# SoilMoisture.net
KiCad netlist of a schematic drawn in EAGLE
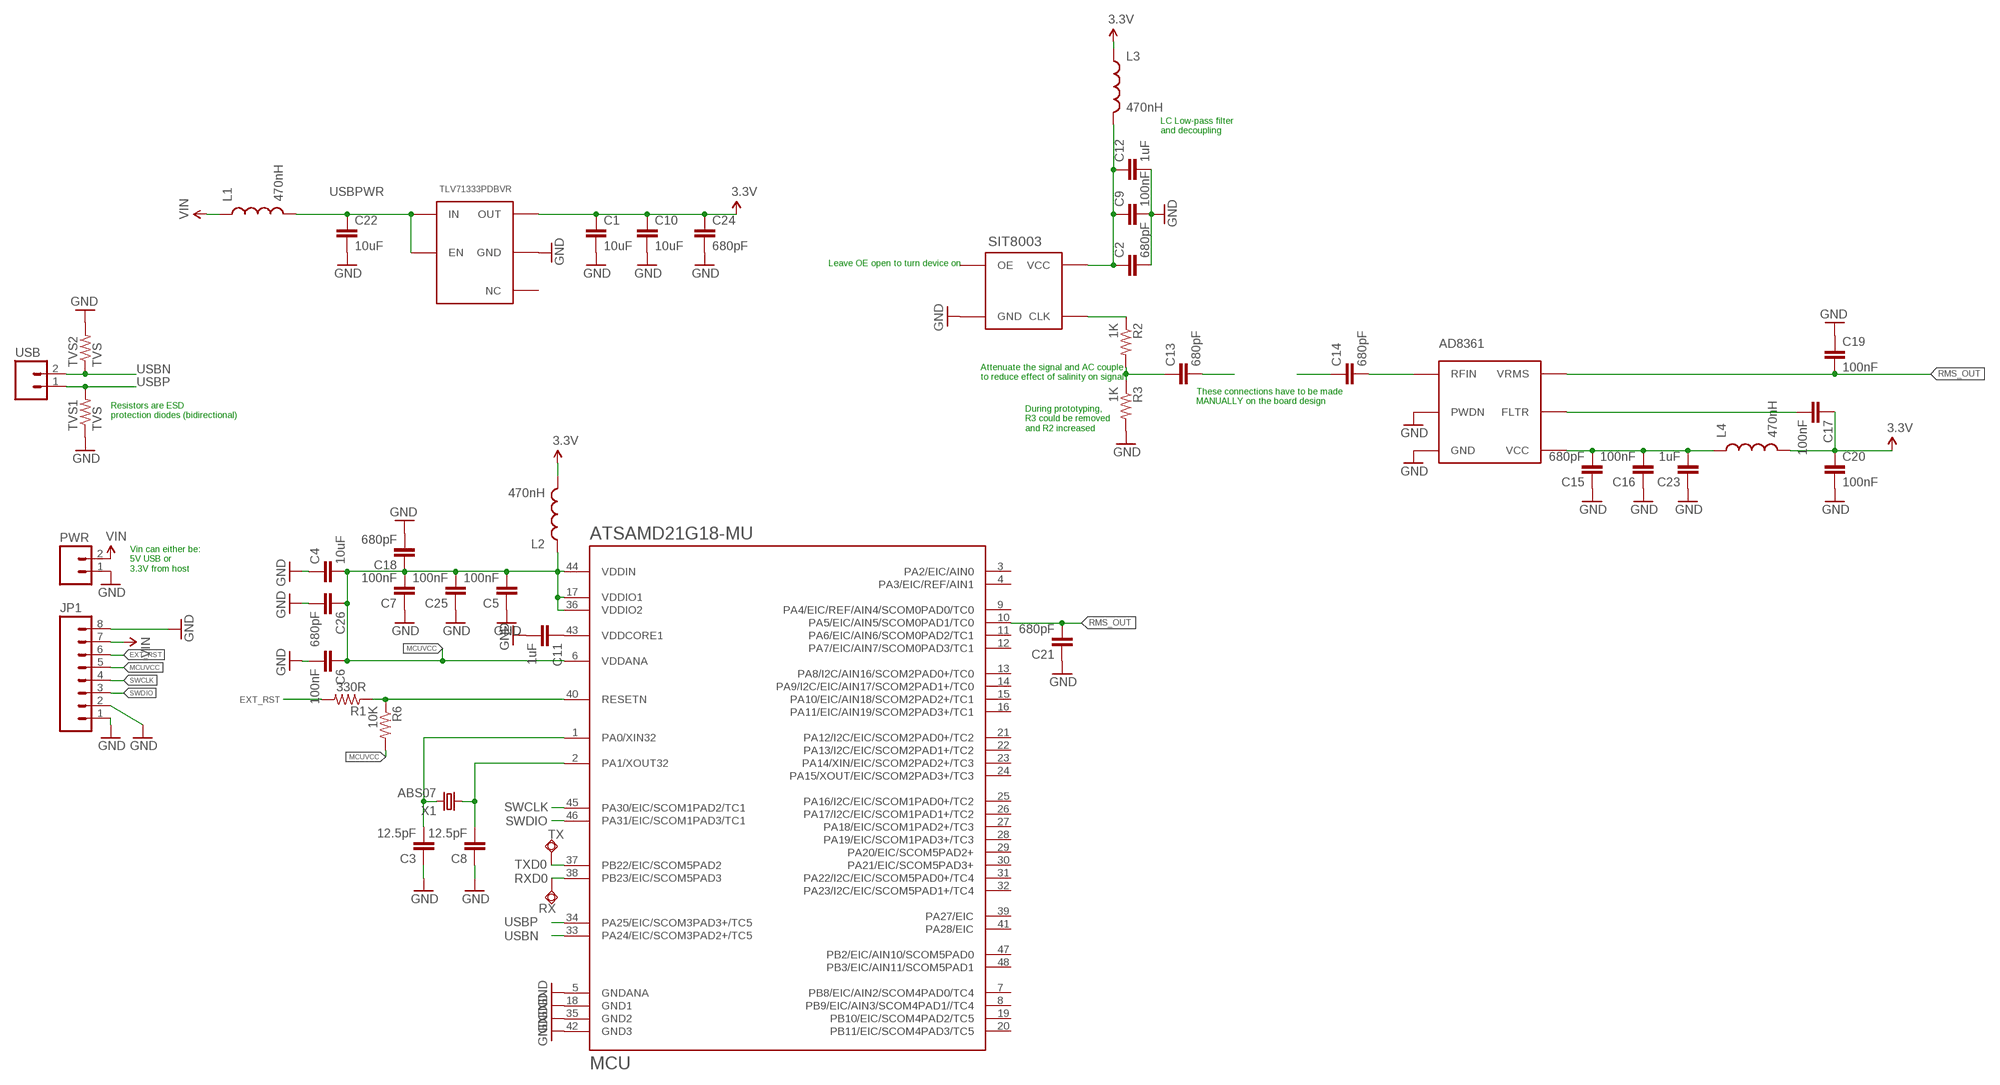
[diagram p0: schematic, sheet 1]

(export (version "E")
  (design (tool "Eeschema 10.0.6"))
  (components
    (comp (ref "AD8361")
      (value "AD8361")
      (footprint "eagle-import:SOT23-6")
      (libsource (lib "eagle-import") (part "AD8361"))
    )
    (comp (ref "C1")
      (value "10uF")
      (footprint "eagle-import:C0603")
      (libsource (lib "eagle-import") (part "C_0603"))
    )
    (comp (ref "C2")
      (value "680pF")
      (footprint "eagle-import:0402-CAP")
      (libsource (lib "eagle-import") (part "CAP0402-CAP"))
    )
    (comp (ref "C3")
      (value "12.5pF")
      (footprint "eagle-import:0402-CAP")
      (libsource (lib "eagle-import") (part "CAP0402-CAP"))
    )
    (comp (ref "C4")
      (value "10uF")
      (footprint "eagle-import:C0603")
      (libsource (lib "eagle-import") (part "C_0603"))
    )
    (comp (ref "C5")
      (value "100nF")
      (footprint "eagle-import:0402-CAP")
      (libsource (lib "eagle-import") (part "CAP0402-CAP"))
    )
    (comp (ref "C6")
      (value "100nF")
      (footprint "eagle-import:0402-CAP")
      (libsource (lib "eagle-import") (part "CAP0402-CAP"))
    )
    (comp (ref "C7")
      (value "100nF")
      (footprint "eagle-import:0402-CAP")
      (libsource (lib "eagle-import") (part "CAP0402-CAP"))
    )
    (comp (ref "C8")
      (value "12.5pF")
      (footprint "eagle-import:0402-CAP")
      (libsource (lib "eagle-import") (part "CAP0402-CAP"))
    )
    (comp (ref "C9")
      (value "100nF")
      (footprint "eagle-import:0402-CAP")
      (libsource (lib "eagle-import") (part "CAP0402-CAP"))
    )
    (comp (ref "C10")
      (value "10uF")
      (footprint "eagle-import:C0603")
      (libsource (lib "eagle-import") (part "C_0603"))
    )
    (comp (ref "C11")
      (value "1uF")
      (footprint "eagle-import:0402-CAP")
      (libsource (lib "eagle-import") (part "CAP0402-CAP"))
    )
    (comp (ref "C12")
      (value "1uF")
      (footprint "eagle-import:0402-CAP")
      (libsource (lib "eagle-import") (part "CAP0402-CAP"))
    )
    (comp (ref "C13")
      (value "680pF")
      (footprint "eagle-import:0402-CAP")
      (libsource (lib "eagle-import") (part "CAP0402-CAP"))
    )
    (comp (ref "C14")
      (value "680pF")
      (footprint "eagle-import:0402-CAP")
      (libsource (lib "eagle-import") (part "CAP0402-CAP"))
    )
    (comp (ref "C15")
      (value "680pF")
      (footprint "eagle-import:0402-CAP")
      (libsource (lib "eagle-import") (part "CAP0402-CAP"))
    )
    (comp (ref "C16")
      (value "100nF")
      (footprint "eagle-import:0402-CAP")
      (libsource (lib "eagle-import") (part "CAP0402-CAP"))
    )
    (comp (ref "C17")
      (value "100nF")
      (footprint "eagle-import:0402-CAP")
      (libsource (lib "eagle-import") (part "CAP0402-CAP"))
    )
    (comp (ref "C18")
      (value "680pF")
      (footprint "eagle-import:0402-CAP")
      (libsource (lib "eagle-import") (part "CAP0402-CAP"))
    )
    (comp (ref "C19")
      (value "100nF")
      (footprint "eagle-import:0402-CAP")
      (libsource (lib "eagle-import") (part "CAP0402-CAP"))
    )
    (comp (ref "C20")
      (value "100nF")
      (footprint "eagle-import:0402-CAP")
      (libsource (lib "eagle-import") (part "CAP0402-CAP"))
    )
    (comp (ref "C21")
      (value "680pF")
      (footprint "eagle-import:0402-CAP")
      (libsource (lib "eagle-import") (part "CAP0402-CAP"))
    )
    (comp (ref "C22")
      (value "10uF")
      (footprint "eagle-import:C0603")
      (libsource (lib "eagle-import") (part "C_0603"))
    )
    (comp (ref "C23")
      (value "1uF")
      (footprint "eagle-import:0402-CAP")
      (libsource (lib "eagle-import") (part "CAP0402-CAP"))
    )
    (comp (ref "C24")
      (value "680pF")
      (footprint "eagle-import:0402-CAP")
      (libsource (lib "eagle-import") (part "CAP0402-CAP"))
    )
    (comp (ref "C25")
      (value "100nF")
      (footprint "eagle-import:0402-CAP")
      (libsource (lib "eagle-import") (part "CAP0402-CAP"))
    )
    (comp (ref "C26")
      (value "680pF")
      (footprint "eagle-import:0402-CAP")
      (libsource (lib "eagle-import") (part "CAP0402-CAP"))
    )
    (comp (ref "JP1")
      (value "M08")
      (footprint "eagle-import:1X08_ROUND")
      (libsource (lib "eagle-import") (part "M08"))
    )
    (comp (ref "L1")
      (value "470nH")
      (footprint "eagle-import:0603")
      (libsource (lib "eagle-import") (part "INDUCTOR0603"))
    )
    (comp (ref "L2")
      (value "470nH")
      (footprint "eagle-import:0603")
      (libsource (lib "eagle-import") (part "INDUCTOR0603"))
    )
    (comp (ref "L3")
      (value "470nH")
      (footprint "eagle-import:0603")
      (libsource (lib "eagle-import") (part "INDUCTOR0603"))
    )
    (comp (ref "L4")
      (value "470nH")
      (footprint "eagle-import:0603")
      (libsource (lib "eagle-import") (part "INDUCTOR0603"))
    )
    (comp (ref "MCU")
      (value "ATSAMD21G18-MU")
      (footprint "eagle-import:QFN48")
      (libsource (lib "eagle-import") (part "ATSAMD21G18-MU"))
    )
    (comp (ref "PWR")
      (value "M02LOCK_LONGPADS")
      (footprint "eagle-import:1X02_LOCK_LONGPADS")
      (libsource (lib "eagle-import") (part "M02LOCK_LONGPADS"))
    )
    (comp (ref "R1")
      (value "330R")
      (footprint "eagle-import:0402-RES")
      (libsource (lib "eagle-import") (part "RESISTOR0402-RES"))
    )
    (comp (ref "R2")
      (value "1K")
      (footprint "eagle-import:0402-RES")
      (libsource (lib "eagle-import") (part "RESISTOR0402-RES"))
    )
    (comp (ref "R3")
      (value "1K")
      (footprint "eagle-import:0402-RES")
      (libsource (lib "eagle-import") (part "RESISTOR0402-RES"))
    )
    (comp (ref "R6")
      (value "10K")
      (footprint "eagle-import:0402-RES")
      (libsource (lib "eagle-import") (part "RESISTOR0402-RES"))
    )
    (comp (ref "REGULATOR")
      (value "TLV71333PDBVR")
      (footprint "eagle-import:TLV71333PDBVR")
      (libsource (lib "eagle-import") (part "TLV71333PDBVR"))
    )
    (comp (ref "RX")
      (value "TPSQTP20SQ")
      (footprint "eagle-import:TP20SQ")
      (libsource (lib "eagle-import") (part "TPSQTP20SQ"))
    )
    (comp (ref "SIT8003")
      (value "SIT8003")
      (footprint "eagle-import:SIT8003")
      (libsource (lib "eagle-import") (part "SIT8003"))
    )
    (comp (ref "TVS1")
      (value "TVS")
      (footprint "eagle-import:0402-RES")
      (libsource (lib "eagle-import") (part "RESISTOR0402-RES"))
    )
    (comp (ref "TVS2")
      (value "TVS")
      (footprint "eagle-import:0402-RES")
      (libsource (lib "eagle-import") (part "RESISTOR0402-RES"))
    )
    (comp (ref "TX")
      (value "TPSQTP20SQ")
      (footprint "eagle-import:TP20SQ")
      (libsource (lib "eagle-import") (part "TPSQTP20SQ"))
    )
    (comp (ref "USB")
      (value "M02LOCK_LONGPADS")
      (footprint "eagle-import:1X02_LOCK_LONGPADS")
      (libsource (lib "eagle-import") (part "M02LOCK_LONGPADS"))
    )
    (comp (ref "X1")
      (value "ABS07")
      (footprint "eagle-import:ABS07")
      (libsource (lib "eagle-import") (part "ABS07"))
    )
  )
  (nets
    (net (code "1") (name "/RXD0") (class "Default")
      (node (ref "MCU") (pin "38") (pinfunction "PB23/EIC/SCOM5PAD3_38") (pintype "bidirectional"))
      (node (ref "RX") (pin "TP") (pinfunction "TP_TP") (pintype "input"))
    )
    (net (code "2") (name "/TXD0") (class "Default")
      (node (ref "MCU") (pin "37") (pinfunction "PB22/EIC/SCOM5PAD2_37") (pintype "bidirectional"))
      (node (ref "TX") (pin "TP") (pinfunction "TP_TP") (pintype "input"))
    )
    (net (code "3") (name "/USBN") (class "Default")
      (node (ref "MCU") (pin "33") (pinfunction "PA24/EIC/SCOM3PAD2+/TC5_33") (pintype "bidirectional"))
      (node (ref "TVS2") (pin "1") (pinfunction "1_1") (pintype "passive"))
      (node (ref "USB") (pin "2") (pinfunction "2_2") (pintype "passive"))
    )
    (net (code "4") (name "/USBP") (class "Default")
      (node (ref "MCU") (pin "34") (pinfunction "PA25/EIC/SCOM3PAD3+/TC5_34") (pintype "bidirectional"))
      (node (ref "TVS1") (pin "2") (pinfunction "2_2") (pintype "passive"))
      (node (ref "USB") (pin "1") (pinfunction "1_1") (pintype "passive"))
    )
    (net (code "5") (name "/USBPWR") (class "Default")
      (node (ref "C22") (pin "1") (pinfunction "1_1") (pintype "passive"))
      (node (ref "L1") (pin "2") (pinfunction "2_2") (pintype "passive"))
      (node (ref "REGULATOR") (pin "P$1") (pinfunction "IN_P$1") (pintype "bidirectional"))
      (node (ref "REGULATOR") (pin "P$3") (pinfunction "EN_P$3") (pintype "bidirectional"))
    )
    (net (code "6") (name "3.3V") (class "Default")
      (node (ref "C1") (pin "1") (pinfunction "1_1") (pintype "passive"))
      (node (ref "C10") (pin "1") (pinfunction "1_1") (pintype "passive"))
      (node (ref "C17") (pin "1") (pinfunction "1_1") (pintype "passive"))
      (node (ref "C20") (pin "1") (pinfunction "1_1") (pintype "passive"))
      (node (ref "C24") (pin "1") (pinfunction "1_1") (pintype "passive"))
      (node (ref "L2") (pin "2") (pinfunction "2_2") (pintype "passive"))
      (node (ref "L3") (pin "1") (pinfunction "1_1") (pintype "passive"))
      (node (ref "L4") (pin "2") (pinfunction "2_2") (pintype "passive"))
      (node (ref "REGULATOR") (pin "P$5") (pinfunction "OUT_P$5") (pintype "bidirectional"))
    )
    (net (code "7") (name "EXT_RST") (class "Default")
      (node (ref "JP1") (pin "6") (pinfunction "6_6") (pintype "passive"))
      (node (ref "R1") (pin "2") (pinfunction "2_2") (pintype "passive"))
    )
    (net (code "8") (name "GND") (class "Default")
      (node (ref "AD8361") (pin "2") (pinfunction "GND_2") (pintype "bidirectional"))
      (node (ref "AD8361") (pin "4") (pinfunction "PWDN_4") (pintype "bidirectional"))
      (node (ref "C1") (pin "2") (pinfunction "2_2") (pintype "passive"))
      (node (ref "C10") (pin "2") (pinfunction "2_2") (pintype "passive"))
      (node (ref "C11") (pin "2") (pinfunction "2_2") (pintype "passive"))
      (node (ref "C12") (pin "2") (pinfunction "2_2") (pintype "passive"))
      (node (ref "C15") (pin "1") (pinfunction "1_1") (pintype "passive"))
      (node (ref "C16") (pin "1") (pinfunction "1_1") (pintype "passive"))
      (node (ref "C18") (pin "2") (pinfunction "2_2") (pintype "passive"))
      (node (ref "C19") (pin "1") (pinfunction "1_1") (pintype "passive"))
      (node (ref "C2") (pin "2") (pinfunction "2_2") (pintype "passive"))
      (node (ref "C20") (pin "2") (pinfunction "2_2") (pintype "passive"))
      (node (ref "C21") (pin "1") (pinfunction "1_1") (pintype "passive"))
      (node (ref "C22") (pin "2") (pinfunction "2_2") (pintype "passive"))
      (node (ref "C23") (pin "1") (pinfunction "1_1") (pintype "passive"))
      (node (ref "C24") (pin "2") (pinfunction "2_2") (pintype "passive"))
      (node (ref "C25") (pin "1") (pinfunction "1_1") (pintype "passive"))
      (node (ref "C26") (pin "2") (pinfunction "2_2") (pintype "passive"))
      (node (ref "C3") (pin "1") (pinfunction "1_1") (pintype "passive"))
      (node (ref "C4") (pin "1") (pinfunction "1_1") (pintype "passive"))
      (node (ref "C5") (pin "1") (pinfunction "1_1") (pintype "passive"))
      (node (ref "C6") (pin "2") (pinfunction "2_2") (pintype "passive"))
      (node (ref "C7") (pin "1") (pinfunction "1_1") (pintype "passive"))
      (node (ref "C8") (pin "1") (pinfunction "1_1") (pintype "passive"))
      (node (ref "C9") (pin "2") (pinfunction "2_2") (pintype "passive"))
      (node (ref "JP1") (pin "1") (pinfunction "1_1") (pintype "passive"))
      (node (ref "JP1") (pin "2") (pinfunction "2_2") (pintype "passive"))
      (node (ref "JP1") (pin "8") (pinfunction "8_8") (pintype "passive"))
      (node (ref "MCU") (pin "18") (pinfunction "GND1_18") (pintype "power_in"))
      (node (ref "MCU") (pin "35") (pinfunction "GND2_35") (pintype "power_in"))
      (node (ref "MCU") (pin "42") (pinfunction "GND3_42") (pintype "power_in"))
      (node (ref "MCU") (pin "5") (pinfunction "GNDANA_5") (pintype "power_in"))
      (node (ref "PWR") (pin "1") (pinfunction "1_1") (pintype "passive"))
      (node (ref "R3") (pin "2") (pinfunction "2_2") (pintype "passive"))
      (node (ref "REGULATOR") (pin "P$2") (pinfunction "GND_P$2") (pintype "bidirectional"))
      (node (ref "SIT8003") (pin "P$2") (pinfunction "GND_P$2") (pintype "bidirectional"))
      (node (ref "TVS1") (pin "1") (pinfunction "1_1") (pintype "passive"))
      (node (ref "TVS2") (pin "2") (pinfunction "2_2") (pintype "passive"))
    )
    (net (code "9") (name "MCUVCC") (class "Default")
      (node (ref "C18") (pin "1") (pinfunction "1_1") (pintype "passive"))
      (node (ref "C25") (pin "2") (pinfunction "2_2") (pintype "passive"))
      (node (ref "C26") (pin "1") (pinfunction "1_1") (pintype "passive"))
      (node (ref "C4") (pin "2") (pinfunction "2_2") (pintype "passive"))
      (node (ref "C5") (pin "2") (pinfunction "2_2") (pintype "passive"))
      (node (ref "C6") (pin "1") (pinfunction "1_1") (pintype "passive"))
      (node (ref "C7") (pin "2") (pinfunction "2_2") (pintype "passive"))
      (node (ref "JP1") (pin "5") (pinfunction "5_5") (pintype "passive"))
      (node (ref "L2") (pin "1") (pinfunction "1_1") (pintype "passive"))
      (node (ref "MCU") (pin "17") (pinfunction "VDDIO1_17") (pintype "power_in"))
      (node (ref "MCU") (pin "36") (pinfunction "VDDIO2_36") (pintype "power_in"))
      (node (ref "MCU") (pin "44") (pinfunction "VDDIN_44") (pintype "power_in"))
      (node (ref "MCU") (pin "6") (pinfunction "VDDANA_6") (pintype "power_in"))
      (node (ref "R6") (pin "2") (pinfunction "2_2") (pintype "passive"))
    )
    (net (code "10") (name "Net-(AD8361-FLTR)") (class "Default")
      (node (ref "AD8361") (pin "3") (pinfunction "FLTR_3") (pintype "bidirectional"))
      (node (ref "C17") (pin "2") (pinfunction "2_2") (pintype "passive"))
    )
    (net (code "11") (name "Net-(AD8361-RFIN)") (class "Default")
      (node (ref "AD8361") (pin "5") (pinfunction "RFIN_5") (pintype "bidirectional"))
      (node (ref "C14") (pin "2") (pinfunction "2_2") (pintype "passive"))
    )
    (net (code "12") (name "Net-(AD8361-VCC)") (class "Default")
      (node (ref "AD8361") (pin "6") (pinfunction "VCC_6") (pintype "bidirectional"))
      (node (ref "C15") (pin "2") (pinfunction "2_2") (pintype "passive"))
      (node (ref "C16") (pin "2") (pinfunction "2_2") (pintype "passive"))
      (node (ref "C23") (pin "2") (pinfunction "2_2") (pintype "passive"))
      (node (ref "L4") (pin "1") (pinfunction "1_1") (pintype "passive"))
    )
    (net (code "13") (name "Net-(C13-Pad1)") (class "Default")
      (node (ref "C13") (pin "1") (pinfunction "1_1") (pintype "passive"))
      (node (ref "R2") (pin "2") (pinfunction "2_2") (pintype "passive"))
      (node (ref "R3") (pin "1") (pinfunction "1_1") (pintype "passive"))
    )
    (net (code "14") (name "Net-(MCU-PA0{slash}XIN32)") (class "Default")
      (node (ref "C3") (pin "2") (pinfunction "2_2") (pintype "passive"))
      (node (ref "MCU") (pin "1") (pinfunction "PA0/XIN32_1") (pintype "bidirectional"))
      (node (ref "X1") (pin "P$2") (pinfunction "2_P$2") (pintype "passive"))
    )
    (net (code "15") (name "Net-(MCU-PA1{slash}XOUT32)") (class "Default")
      (node (ref "C8") (pin "2") (pinfunction "2_2") (pintype "passive"))
      (node (ref "MCU") (pin "2") (pinfunction "PA1/XOUT32_2") (pintype "bidirectional"))
      (node (ref "X1") (pin "P$1") (pinfunction "1_P$1") (pintype "passive"))
    )
    (net (code "16") (name "Net-(MCU-RESETN)") (class "Default")
      (node (ref "MCU") (pin "40") (pinfunction "RESETN_40") (pintype "bidirectional"))
      (node (ref "R1") (pin "1") (pinfunction "1_1") (pintype "passive"))
      (node (ref "R6") (pin "1") (pinfunction "1_1") (pintype "passive"))
    )
    (net (code "17") (name "Net-(MCU-VDDCORE1)") (class "Default")
      (node (ref "C11") (pin "1") (pinfunction "1_1") (pintype "passive"))
      (node (ref "MCU") (pin "43") (pinfunction "VDDCORE1_43") (pintype "input"))
    )
    (net (code "18") (name "Net-(SIT8003-CLK)") (class "Default")
      (node (ref "R2") (pin "1") (pinfunction "1_1") (pintype "passive"))
      (node (ref "SIT8003") (pin "P$3") (pinfunction "CLK_P$3") (pintype "bidirectional"))
    )
    (net (code "19") (name "Net-(SIT8003-VCC)") (class "Default")
      (node (ref "C12") (pin "1") (pinfunction "1_1") (pintype "passive"))
      (node (ref "C2") (pin "1") (pinfunction "1_1") (pintype "passive"))
      (node (ref "C9") (pin "1") (pinfunction "1_1") (pintype "passive"))
      (node (ref "L3") (pin "2") (pinfunction "2_2") (pintype "passive"))
      (node (ref "SIT8003") (pin "P$4") (pinfunction "VCC_P$4") (pintype "bidirectional"))
    )
    (net (code "20") (name "RMS_OUT") (class "Default")
      (node (ref "AD8361") (pin "1") (pinfunction "VRMS_1") (pintype "bidirectional"))
      (node (ref "C19") (pin "2") (pinfunction "2_2") (pintype "passive"))
      (node (ref "C21") (pin "2") (pinfunction "2_2") (pintype "passive"))
      (node (ref "MCU") (pin "10") (pinfunction "PA5/EIC/AIN5/SCOM0PAD1/TC0_10") (pintype "bidirectional"))
    )
    (net (code "21") (name "SWCLK") (class "Default")
      (node (ref "JP1") (pin "4") (pinfunction "4_4") (pintype "passive"))
      (node (ref "MCU") (pin "45") (pinfunction "PA30/EIC/SCOM1PAD2/TC1_45") (pintype "bidirectional"))
    )
    (net (code "22") (name "SWDIO") (class "Default")
      (node (ref "JP1") (pin "3") (pinfunction "3_3") (pintype "passive"))
      (node (ref "MCU") (pin "46") (pinfunction "PA31/EIC/SCOM1PAD3/TC1_46") (pintype "bidirectional"))
    )
    (net (code "23") (name "VIN") (class "Default")
      (node (ref "JP1") (pin "7") (pinfunction "7_7") (pintype "passive"))
      (node (ref "L1") (pin "1") (pinfunction "1_1") (pintype "passive"))
      (node (ref "PWR") (pin "2") (pinfunction "2_2") (pintype "passive"))
    )
    (net (code "24") (name "unconnected-(C13-Pad2)") (class "Default")
      (node (ref "C13") (pin "2") (pinfunction "2_2") (pintype "passive"))
    )
    (net (code "25") (name "unconnected-(C14-Pad1)") (class "Default")
      (node (ref "C14") (pin "1") (pinfunction "1_1") (pintype "passive"))
    )
    (net (code "26") (name "unconnected-(MCU-PA2{slash}EIC{slash}AIN0-Pad3)") (class "Default")
      (node (ref "MCU") (pin "3") (pinfunction "PA2/EIC/AIN0_3") (pintype "bidirectional"))
    )
    (net (code "27") (name "unconnected-(MCU-PA3{slash}EIC{slash}REF{slash}AIN1-Pad4)") (class "Default")
      (node (ref "MCU") (pin "4") (pinfunction "PA3/EIC/REF/AIN1_4") (pintype "bidirectional"))
    )
    (net (code "28") (name "unconnected-(MCU-PA4{slash}EIC{slash}REF{slash}AIN4{slash}SCOM0PAD0{slash}TC0-Pad9)") (class "Default")
      (node (ref "MCU") (pin "9") (pinfunction "PA4/EIC/REF/AIN4/SCOM0PAD0/TC0_9") (pintype "bidirectional"))
    )
    (net (code "29") (name "unconnected-(MCU-PA6{slash}EIC{slash}AIN6{slash}SCOM0PAD2{slash}TC1-Pad11)") (class "Default")
      (node (ref "MCU") (pin "11") (pinfunction "PA6/EIC/AIN6/SCOM0PAD2/TC1_11") (pintype "bidirectional"))
    )
    (net (code "30") (name "unconnected-(MCU-PA7{slash}EIC{slash}AIN7{slash}SCOM0PAD3{slash}TC1-Pad12)") (class "Default")
      (node (ref "MCU") (pin "12") (pinfunction "PA7/EIC/AIN7/SCOM0PAD3/TC1_12") (pintype "bidirectional"))
    )
    (net (code "31") (name "unconnected-(MCU-PA8{slash}I2C{slash}AIN16{slash}SCOM2PAD0+{slash}TC0-Pad13)") (class "Default")
      (node (ref "MCU") (pin "13") (pinfunction "PA8/I2C/AIN16/SCOM2PAD0+/TC0_13") (pintype "bidirectional"))
    )
    (net (code "32") (name "unconnected-(MCU-PA9{slash}I2C{slash}EIC{slash}AIN17{slash}SCOM2PAD1+{slash}TC0-Pad14)") (class "Default")
      (node (ref "MCU") (pin "14") (pinfunction "PA9/I2C/EIC/AIN17/SCOM2PAD1+/TC0_14") (pintype "bidirectional"))
    )
    (net (code "33") (name "unconnected-(MCU-PA10{slash}EIC{slash}AIN18{slash}SCOM2PAD2+{slash}TC1-Pad15)") (class "Default")
      (node (ref "MCU") (pin "15") (pinfunction "PA10/EIC/AIN18/SCOM2PAD2+/TC1_15") (pintype "bidirectional"))
    )
    (net (code "34") (name "unconnected-(MCU-PA11{slash}EIC{slash}AIN19{slash}SCOM2PAD3+{slash}TC1-Pad16)") (class "Default")
      (node (ref "MCU") (pin "16") (pinfunction "PA11/EIC/AIN19/SCOM2PAD3+/TC1_16") (pintype "bidirectional"))
    )
    (net (code "35") (name "unconnected-(MCU-PA12{slash}I2C{slash}EIC{slash}SCOM2PAD0+{slash}TC2-Pad21)") (class "Default")
      (node (ref "MCU") (pin "21") (pinfunction "PA12/I2C/EIC/SCOM2PAD0+/TC2_21") (pintype "bidirectional"))
    )
    (net (code "36") (name "unconnected-(MCU-PA13{slash}I2C{slash}EIC{slash}SCOM2PAD1+{slash}TC2-Pad22)") (class "Default")
      (node (ref "MCU") (pin "22") (pinfunction "PA13/I2C/EIC/SCOM2PAD1+/TC2_22") (pintype "bidirectional"))
    )
    (net (code "37") (name "unconnected-(MCU-PA14{slash}XIN{slash}EIC{slash}SCOM2PAD2+{slash}TC3-Pad23)") (class "Default")
      (node (ref "MCU") (pin "23") (pinfunction "PA14/XIN/EIC/SCOM2PAD2+/TC3_23") (pintype "bidirectional"))
    )
    (net (code "38") (name "unconnected-(MCU-PA15{slash}XOUT{slash}EIC{slash}SCOM2PAD3+{slash}TC3-Pad24)") (class "Default")
      (node (ref "MCU") (pin "24") (pinfunction "PA15/XOUT/EIC/SCOM2PAD3+/TC3_24") (pintype "bidirectional"))
    )
    (net (code "39") (name "unconnected-(MCU-PA16{slash}I2C{slash}EIC{slash}SCOM1PAD0+{slash}TC2-Pad25)") (class "Default")
      (node (ref "MCU") (pin "25") (pinfunction "PA16/I2C/EIC/SCOM1PAD0+/TC2_25") (pintype "bidirectional"))
    )
    (net (code "40") (name "unconnected-(MCU-PA17{slash}I2C{slash}EIC{slash}SCOM1PAD1+{slash}TC2-Pad26)") (class "Default")
      (node (ref "MCU") (pin "26") (pinfunction "PA17/I2C/EIC/SCOM1PAD1+/TC2_26") (pintype "bidirectional"))
    )
    (net (code "41") (name "unconnected-(MCU-PA18{slash}EIC{slash}SCOM1PAD2+{slash}TC3-Pad27)") (class "Default")
      (node (ref "MCU") (pin "27") (pinfunction "PA18/EIC/SCOM1PAD2+/TC3_27") (pintype "bidirectional"))
    )
    (net (code "42") (name "unconnected-(MCU-PA19{slash}EIC{slash}SCOM1PAD3+{slash}TC3-Pad28)") (class "Default")
      (node (ref "MCU") (pin "28") (pinfunction "PA19/EIC/SCOM1PAD3+/TC3_28") (pintype "bidirectional"))
    )
    (net (code "43") (name "unconnected-(MCU-PA20{slash}EIC{slash}SCOM5PAD2+-Pad29)") (class "Default")
      (node (ref "MCU") (pin "29") (pinfunction "PA20/EIC/SCOM5PAD2+_29") (pintype "bidirectional"))
    )
    (net (code "44") (name "unconnected-(MCU-PA21{slash}EIC{slash}SCOM5PAD3+-Pad30)") (class "Default")
      (node (ref "MCU") (pin "30") (pinfunction "PA21/EIC/SCOM5PAD3+_30") (pintype "bidirectional"))
    )
    (net (code "45") (name "unconnected-(MCU-PA22{slash}I2C{slash}EIC{slash}SCOM5PAD0+{slash}TC4-Pad31)") (class "Default")
      (node (ref "MCU") (pin "31") (pinfunction "PA22/I2C/EIC/SCOM5PAD0+/TC4_31") (pintype "bidirectional"))
    )
    (net (code "46") (name "unconnected-(MCU-PA23{slash}I2C{slash}EIC{slash}SCOM5PAD1+{slash}TC4-Pad32)") (class "Default")
      (node (ref "MCU") (pin "32") (pinfunction "PA23/I2C/EIC/SCOM5PAD1+/TC4_32") (pintype "bidirectional"))
    )
    (net (code "47") (name "unconnected-(MCU-PA27{slash}EIC-Pad39)") (class "Default")
      (node (ref "MCU") (pin "39") (pinfunction "PA27/EIC_39") (pintype "bidirectional"))
    )
    (net (code "48") (name "unconnected-(MCU-PA28{slash}EIC-Pad41)") (class "Default")
      (node (ref "MCU") (pin "41") (pinfunction "PA28/EIC_41") (pintype "bidirectional"))
    )
    (net (code "49") (name "unconnected-(MCU-PB2{slash}EIC{slash}AIN10{slash}SCOM5PAD0-Pad47)") (class "Default")
      (node (ref "MCU") (pin "47") (pinfunction "PB2/EIC/AIN10/SCOM5PAD0_47") (pintype "bidirectional"))
    )
    (net (code "50") (name "unconnected-(MCU-PB3{slash}EIC{slash}AIN11{slash}SCOM5PAD1-Pad48)") (class "Default")
      (node (ref "MCU") (pin "48") (pinfunction "PB3/EIC/AIN11/SCOM5PAD1_48") (pintype "bidirectional"))
    )
    (net (code "51") (name "unconnected-(MCU-PB8{slash}EIC{slash}AIN2{slash}SCOM4PAD0{slash}TC4-Pad7)") (class "Default")
      (node (ref "MCU") (pin "7") (pinfunction "PB8/EIC/AIN2/SCOM4PAD0/TC4_7") (pintype "bidirectional"))
    )
    (net (code "52") (name "unconnected-(MCU-PB9{slash}EIC{slash}AIN3{slash}SCOM4PAD1{slash}{slash}TC4-Pad8)") (class "Default")
      (node (ref "MCU") (pin "8") (pinfunction "PB9/EIC/AIN3/SCOM4PAD1//TC4_8") (pintype "bidirectional"))
    )
    (net (code "53") (name "unconnected-(MCU-PB10{slash}EIC{slash}SCOM4PAD2{slash}TC5-Pad19)") (class "Default")
      (node (ref "MCU") (pin "19") (pinfunction "PB10/EIC/SCOM4PAD2/TC5_19") (pintype "bidirectional"))
    )
    (net (code "54") (name "unconnected-(MCU-PB11{slash}EIC{slash}SCOM4PAD3{slash}TC5-Pad20)") (class "Default")
      (node (ref "MCU") (pin "20") (pinfunction "PB11/EIC/SCOM4PAD3/TC5_20") (pintype "bidirectional"))
    )
    (net (code "55") (name "unconnected-(REGULATOR-NC-PadP$4)") (class "Default")
      (node (ref "REGULATOR") (pin "P$4") (pinfunction "NC_P$4") (pintype "bidirectional"))
    )
    (net (code "56") (name "unconnected-(SIT8003-OE-PadP$1)") (class "Default")
      (node (ref "SIT8003") (pin "P$1") (pinfunction "OE_P$1") (pintype "bidirectional"))
    )
  )
)
